# Main_Electronics_B.net
KiCad netlist of a schematic drawn in EAGLE
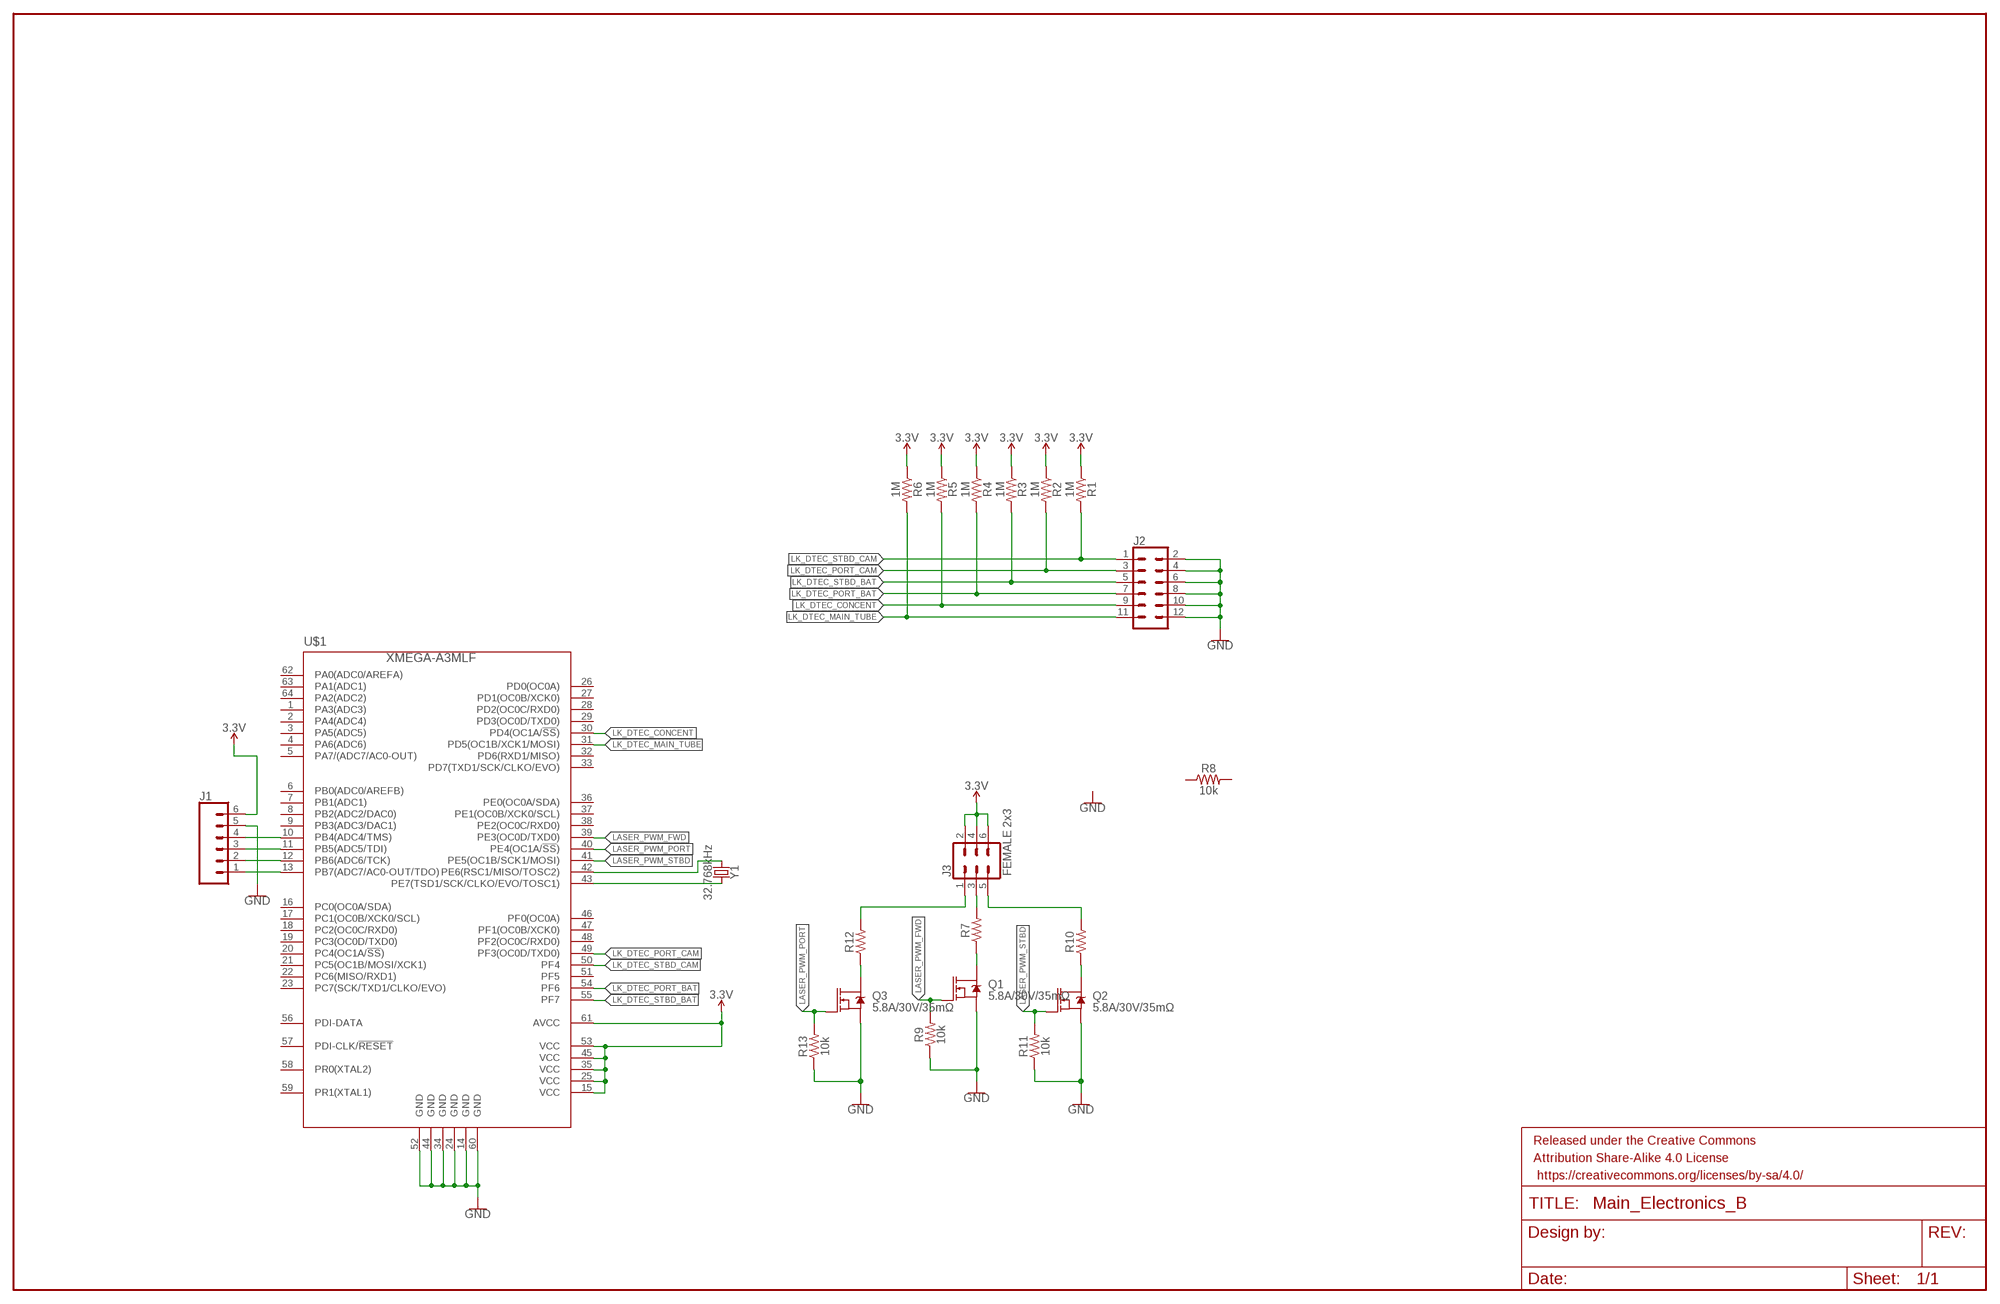
[diagram p0: schematic, sheet 1]

(export (version "E")
  (design (tool "Eeschema 10.0.6"))
  (components
    (comp (ref "FRAME1")
      (value "FRAME-LEDGER")
      (footprint "eagle-import:CREATIVE_COMMONS")
      (libsource (lib "eagle-import") (part "FRAME-LEDGER"))
    )
    (comp (ref "J1")
      (value "CONN_06NO_SILK_NO_POP")
      (footprint "eagle-import:1X06_NO_SILK")
      (libsource (lib "eagle-import") (part "CONN_06NO_SILK_NO_POP"))
    )
    (comp (ref "J2")
      (value "CONN_06X2NO_SILK")
      (footprint "eagle-import:2X6_NOSILK")
      (libsource (lib "eagle-import") (part "CONN_06X2NO_SILK"))
    )
    (comp (ref "J3")
      (value "FEMALE 2x3")
      (footprint "eagle-import:2X3")
      (libsource (lib "eagle-import") (part "CONN_03X2FEMALE"))
    )
    (comp (ref "Q1")
      (value "5.8A/30V/35mΩ")
      (footprint "eagle-import:SOT23-3")
      (libsource (lib "eagle-import") (part "MOSFET-NCH-AO3404A"))
    )
    (comp (ref "Q2")
      (value "5.8A/30V/35mΩ")
      (footprint "eagle-import:SOT23-3")
      (libsource (lib "eagle-import") (part "MOSFET-NCH-AO3404A"))
    )
    (comp (ref "Q3")
      (value "5.8A/30V/35mΩ")
      (footprint "eagle-import:SOT23-3")
      (libsource (lib "eagle-import") (part "MOSFET-NCH-AO3404A"))
    )
    (comp (ref "R1")
      (value "1M")
      (footprint "eagle-import:0603")
      (libsource (lib "eagle-import") (part "1MOHM-0603-1/4W-5%"))
    )
    (comp (ref "R2")
      (value "1M")
      (footprint "eagle-import:0603")
      (libsource (lib "eagle-import") (part "1MOHM-0603-1/4W-5%"))
    )
    (comp (ref "R3")
      (value "1M")
      (footprint "eagle-import:0603")
      (libsource (lib "eagle-import") (part "1MOHM-0603-1/4W-5%"))
    )
    (comp (ref "R4")
      (value "1M")
      (footprint "eagle-import:0603")
      (libsource (lib "eagle-import") (part "1MOHM-0603-1/4W-5%"))
    )
    (comp (ref "R5")
      (value "1M")
      (footprint "eagle-import:0603")
      (libsource (lib "eagle-import") (part "1MOHM-0603-1/4W-5%"))
    )
    (comp (ref "R6")
      (value "1M")
      (footprint "eagle-import:0603")
      (libsource (lib "eagle-import") (part "1MOHM-0603-1/4W-5%"))
    )
    (comp (ref "R7")
      (value "RESISTOR0603")
      (footprint "eagle-import:0603")
      (libsource (lib "eagle-import") (part "RESISTOR0603"))
    )
    (comp (ref "R8")
      (value "10k")
      (footprint "eagle-import:0603")
      (libsource (lib "eagle-import") (part "10KOHM-0603-1/10W-1%"))
    )
    (comp (ref "R9")
      (value "10k")
      (footprint "eagle-import:0603")
      (libsource (lib "eagle-import") (part "10KOHM-0603-1/10W-1%"))
    )
    (comp (ref "R10")
      (value "RESISTOR0603")
      (footprint "eagle-import:0603")
      (libsource (lib "eagle-import") (part "RESISTOR0603"))
    )
    (comp (ref "R11")
      (value "10k")
      (footprint "eagle-import:0603")
      (libsource (lib "eagle-import") (part "10KOHM-0603-1/10W-1%"))
    )
    (comp (ref "R12")
      (value "RESISTOR0603")
      (footprint "eagle-import:0603")
      (libsource (lib "eagle-import") (part "RESISTOR0603"))
    )
    (comp (ref "R13")
      (value "10k")
      (footprint "eagle-import:0603")
      (libsource (lib "eagle-import") (part "10KOHM-0603-1/10W-1%"))
    )
    (comp (ref "U$1")
      (value "XMEGA-A3MLF")
      (footprint "eagle-import:MLF64")
      (libsource (lib "eagle-import") (part "XMEGA-A3MLF"))
    )
    (comp (ref "Y1")
      (value "32.768kHz")
      (footprint "eagle-import:CRYSTAL-PTH-2X6-CYL-KIT")
      (libsource (lib "eagle-import") (part "CRYSTAL-32.768KHZPTH-2X6-KIT"))
    )
  )
  (nets
    (net (code "1") (name "3.3V") (class "Default")
      (node (ref "J1") (pin "6") (pinfunction "6_6") (pintype "passive"))
      (node (ref "J3") (pin "2") (pinfunction "2_2") (pintype "bidirectional"))
      (node (ref "J3") (pin "4") (pinfunction "4_4") (pintype "bidirectional"))
      (node (ref "J3") (pin "6") (pinfunction "6_6") (pintype "bidirectional"))
      (node (ref "R1") (pin "1") (pinfunction "1_1") (pintype "passive"))
      (node (ref "R2") (pin "1") (pinfunction "1_1") (pintype "passive"))
      (node (ref "R3") (pin "1") (pinfunction "1_1") (pintype "passive"))
      (node (ref "R4") (pin "1") (pinfunction "1_1") (pintype "passive"))
      (node (ref "R5") (pin "1") (pinfunction "1_1") (pintype "passive"))
      (node (ref "R6") (pin "1") (pinfunction "1_1") (pintype "passive"))
      (node (ref "U$1") (pin "15") (pinfunction "VCC_15") (pintype "power_in"))
      (node (ref "U$1") (pin "25") (pinfunction "VCC_25") (pintype "power_in"))
      (node (ref "U$1") (pin "35") (pinfunction "VCC_35") (pintype "power_in"))
      (node (ref "U$1") (pin "45") (pinfunction "VCC_45") (pintype "power_in"))
      (node (ref "U$1") (pin "53") (pinfunction "VCC_53") (pintype "power_in"))
      (node (ref "U$1") (pin "61") (pinfunction "AVCC_61") (pintype "power_in"))
    )
    (net (code "2") (name "GND") (class "Default")
      (node (ref "J1") (pin "5") (pinfunction "5_5") (pintype "passive"))
      (node (ref "J2") (pin "10") (pinfunction "10_10") (pintype "passive"))
      (node (ref "J2") (pin "12") (pinfunction "12_12") (pintype "passive"))
      (node (ref "J2") (pin "2") (pinfunction "2_2") (pintype "passive"))
      (node (ref "J2") (pin "4") (pinfunction "4_4") (pintype "passive"))
      (node (ref "J2") (pin "6") (pinfunction "6_6") (pintype "passive"))
      (node (ref "J2") (pin "8") (pinfunction "8_8") (pintype "passive"))
      (node (ref "Q1") (pin "2") (pinfunction "S_2") (pintype "bidirectional"))
      (node (ref "Q2") (pin "2") (pinfunction "S_2") (pintype "bidirectional"))
      (node (ref "Q3") (pin "2") (pinfunction "S_2") (pintype "bidirectional"))
      (node (ref "R11") (pin "1") (pinfunction "1_1") (pintype "passive"))
      (node (ref "R13") (pin "1") (pinfunction "1_1") (pintype "passive"))
      (node (ref "R9") (pin "1") (pinfunction "1_1") (pintype "passive"))
      (node (ref "U$1") (pin "14") (pinfunction "GND_14") (pintype "power_in"))
      (node (ref "U$1") (pin "24") (pinfunction "GND_24") (pintype "power_in"))
      (node (ref "U$1") (pin "34") (pinfunction "GND_34") (pintype "power_in"))
      (node (ref "U$1") (pin "44") (pinfunction "GND_44") (pintype "power_in"))
      (node (ref "U$1") (pin "52") (pinfunction "GND_52") (pintype "power_in"))
      (node (ref "U$1") (pin "60") (pinfunction "GND_60") (pintype "power_in"))
    )
    (net (code "3") (name "LASER_PWM_FWD") (class "Default")
      (node (ref "Q1") (pin "1") (pinfunction "G_1") (pintype "bidirectional"))
      (node (ref "R9") (pin "2") (pinfunction "2_2") (pintype "passive"))
      (node (ref "U$1") (pin "39") (pinfunction "PE3(OC0D/TXD0)_39") (pintype "bidirectional"))
    )
    (net (code "4") (name "LASER_PWM_PORT") (class "Default")
      (node (ref "Q3") (pin "1") (pinfunction "G_1") (pintype "bidirectional"))
      (node (ref "R13") (pin "2") (pinfunction "2_2") (pintype "passive"))
      (node (ref "U$1") (pin "40") (pinfunction "PE4(OC1A/~{SS})_40") (pintype "bidirectional"))
    )
    (net (code "5") (name "LASER_PWM_STBD") (class "Default")
      (node (ref "Q2") (pin "1") (pinfunction "G_1") (pintype "bidirectional"))
      (node (ref "R11") (pin "2") (pinfunction "2_2") (pintype "passive"))
      (node (ref "U$1") (pin "41") (pinfunction "PE5(OC1B/SCK1/MOSI)_41") (pintype "bidirectional"))
    )
    (net (code "6") (name "LK_DTEC_CONCENT") (class "Default")
      (node (ref "J2") (pin "9") (pinfunction "9_9") (pintype "passive"))
      (node (ref "R5") (pin "2") (pinfunction "2_2") (pintype "passive"))
      (node (ref "U$1") (pin "30") (pinfunction "PD4(OC1A/~{SS})_30") (pintype "bidirectional"))
    )
    (net (code "7") (name "LK_DTEC_MAIN_TUBE") (class "Default")
      (node (ref "J2") (pin "11") (pinfunction "11_11") (pintype "passive"))
      (node (ref "R6") (pin "2") (pinfunction "2_2") (pintype "passive"))
      (node (ref "U$1") (pin "31") (pinfunction "PD5(OC1B/XCK1/MOSI)_31") (pintype "bidirectional"))
    )
    (net (code "8") (name "LK_DTEC_PORT_BAT") (class "Default")
      (node (ref "J2") (pin "7") (pinfunction "7_7") (pintype "passive"))
      (node (ref "R4") (pin "2") (pinfunction "2_2") (pintype "passive"))
      (node (ref "U$1") (pin "54") (pinfunction "PF6_54") (pintype "bidirectional"))
    )
    (net (code "9") (name "LK_DTEC_PORT_CAM") (class "Default")
      (node (ref "J2") (pin "3") (pinfunction "3_3") (pintype "passive"))
      (node (ref "R2") (pin "2") (pinfunction "2_2") (pintype "passive"))
      (node (ref "U$1") (pin "49") (pinfunction "PF3(OC0D/TXD0)_49") (pintype "bidirectional"))
    )
    (net (code "10") (name "LK_DTEC_STBD_BAT") (class "Default")
      (node (ref "J2") (pin "5") (pinfunction "5_5") (pintype "passive"))
      (node (ref "R3") (pin "2") (pinfunction "2_2") (pintype "passive"))
      (node (ref "U$1") (pin "55") (pinfunction "PF7_55") (pintype "bidirectional"))
    )
    (net (code "11") (name "LK_DTEC_STBD_CAM") (class "Default")
      (node (ref "J2") (pin "1") (pinfunction "1_1") (pintype "passive"))
      (node (ref "R1") (pin "2") (pinfunction "2_2") (pintype "passive"))
      (node (ref "U$1") (pin "50") (pinfunction "PF4_50") (pintype "bidirectional"))
    )
    (net (code "12") (name "Net-(J3-Pad1)") (class "Default")
      (node (ref "J3") (pin "1") (pinfunction "1_1") (pintype "bidirectional"))
      (node (ref "R12") (pin "2") (pinfunction "2_2") (pintype "passive"))
    )
    (net (code "13") (name "Net-(J3-Pad3)") (class "Default")
      (node (ref "J3") (pin "3") (pinfunction "3_3") (pintype "bidirectional"))
      (node (ref "R7") (pin "2") (pinfunction "2_2") (pintype "passive"))
    )
    (net (code "14") (name "Net-(J3-Pad5)") (class "Default")
      (node (ref "J3") (pin "5") (pinfunction "5_5") (pintype "bidirectional"))
      (node (ref "R10") (pin "2") (pinfunction "2_2") (pintype "passive"))
    )
    (net (code "15") (name "Net-(Q1-D)") (class "Default")
      (node (ref "Q1") (pin "3") (pinfunction "D_3") (pintype "bidirectional"))
      (node (ref "R7") (pin "1") (pinfunction "1_1") (pintype "passive"))
    )
    (net (code "16") (name "Net-(Q2-D)") (class "Default")
      (node (ref "Q2") (pin "3") (pinfunction "D_3") (pintype "bidirectional"))
      (node (ref "R10") (pin "1") (pinfunction "1_1") (pintype "passive"))
    )
    (net (code "17") (name "Net-(Q3-D)") (class "Default")
      (node (ref "Q3") (pin "3") (pinfunction "D_3") (pintype "bidirectional"))
      (node (ref "R12") (pin "1") (pinfunction "1_1") (pintype "passive"))
    )
    (net (code "18") (name "Net-(U$1-PB4(ADC4{slash}TMS))") (class "Default")
      (node (ref "J1") (pin "4") (pinfunction "4_4") (pintype "passive"))
      (node (ref "U$1") (pin "10") (pinfunction "PB4(ADC4/TMS)_10") (pintype "bidirectional"))
    )
    (net (code "19") (name "Net-(U$1-PB5(ADC5{slash}TDI))") (class "Default")
      (node (ref "J1") (pin "3") (pinfunction "3_3") (pintype "passive"))
      (node (ref "U$1") (pin "11") (pinfunction "PB5(ADC5/TDI)_11") (pintype "bidirectional"))
    )
    (net (code "20") (name "Net-(U$1-PB6(ADC6{slash}TCK))") (class "Default")
      (node (ref "J1") (pin "2") (pinfunction "2_2") (pintype "passive"))
      (node (ref "U$1") (pin "12") (pinfunction "PB6(ADC6/TCK)_12") (pintype "bidirectional"))
    )
    (net (code "21") (name "Net-(U$1-PB7(ADC7{slash}AC0-OUT{slash}TDO))") (class "Default")
      (node (ref "J1") (pin "1") (pinfunction "1_1") (pintype "passive"))
      (node (ref "U$1") (pin "13") (pinfunction "PB7(ADC7/AC0-OUT/TDO)_13") (pintype "bidirectional"))
    )
    (net (code "22") (name "Net-(U$1-PE6(RSC1{slash}MISO{slash}TOSC2))") (class "Default")
      (node (ref "U$1") (pin "42") (pinfunction "PE6(RSC1/MISO/TOSC2)_42") (pintype "bidirectional"))
      (node (ref "Y1") (pin "1") (pinfunction "1_1") (pintype "passive"))
    )
    (net (code "23") (name "Net-(U$1-PE7(TSD1{slash}SCK{slash}CLKO{slash}EVO{slash}TOSC1))") (class "Default")
      (node (ref "U$1") (pin "43") (pinfunction "PE7(TSD1/SCK/CLKO/EVO/TOSC1)_43") (pintype "bidirectional"))
      (node (ref "Y1") (pin "2") (pinfunction "2_2") (pintype "passive"))
    )
    (net (code "24") (name "unconnected-(R8-Pad1)") (class "Default")
      (node (ref "R8") (pin "1") (pinfunction "1_1") (pintype "passive"))
    )
    (net (code "25") (name "unconnected-(R8-Pad2)") (class "Default")
      (node (ref "R8") (pin "2") (pinfunction "2_2") (pintype "passive"))
    )
    (net (code "26") (name "unconnected-(U$1-PA0(ADC0{slash}AREFA)-Pad62)") (class "Default")
      (node (ref "U$1") (pin "62") (pinfunction "PA0(ADC0/AREFA)_62") (pintype "bidirectional"))
    )
    (net (code "27") (name "unconnected-(U$1-PA1(ADC1)-Pad63)") (class "Default")
      (node (ref "U$1") (pin "63") (pinfunction "PA1(ADC1)_63") (pintype "bidirectional"))
    )
    (net (code "28") (name "unconnected-(U$1-PA2(ADC2)-Pad64)") (class "Default")
      (node (ref "U$1") (pin "64") (pinfunction "PA2(ADC2)_64") (pintype "bidirectional"))
    )
    (net (code "29") (name "unconnected-(U$1-PA3(ADC3)-Pad1)") (class "Default")
      (node (ref "U$1") (pin "1") (pinfunction "PA3(ADC3)_1") (pintype "bidirectional"))
    )
    (net (code "30") (name "unconnected-(U$1-PA4(ADC4)-Pad2)") (class "Default")
      (node (ref "U$1") (pin "2") (pinfunction "PA4(ADC4)_2") (pintype "bidirectional"))
    )
    (net (code "31") (name "unconnected-(U$1-PA5(ADC5)-Pad3)") (class "Default")
      (node (ref "U$1") (pin "3") (pinfunction "PA5(ADC5)_3") (pintype "bidirectional"))
    )
    (net (code "32") (name "unconnected-(U$1-PA6(ADC6)-Pad4)") (class "Default")
      (node (ref "U$1") (pin "4") (pinfunction "PA6(ADC6)_4") (pintype "bidirectional"))
    )
    (net (code "33") (name "unconnected-(U$1-PA7{slash}(ADC7{slash}AC0-OUT)-Pad5)") (class "Default")
      (node (ref "U$1") (pin "5") (pinfunction "PA7/(ADC7/AC0-OUT)_5") (pintype "bidirectional"))
    )
    (net (code "34") (name "unconnected-(U$1-PB0(ADC0{slash}AREFB)-Pad6)") (class "Default")
      (node (ref "U$1") (pin "6") (pinfunction "PB0(ADC0/AREFB)_6") (pintype "bidirectional"))
    )
    (net (code "35") (name "unconnected-(U$1-PB1(ADC1)-Pad7)") (class "Default")
      (node (ref "U$1") (pin "7") (pinfunction "PB1(ADC1)_7") (pintype "bidirectional"))
    )
    (net (code "36") (name "unconnected-(U$1-PB2(ADC2{slash}DAC0)-Pad8)") (class "Default")
      (node (ref "U$1") (pin "8") (pinfunction "PB2(ADC2/DAC0)_8") (pintype "bidirectional"))
    )
    (net (code "37") (name "unconnected-(U$1-PB3(ADC3{slash}DAC1)-Pad9)") (class "Default")
      (node (ref "U$1") (pin "9") (pinfunction "PB3(ADC3/DAC1)_9") (pintype "bidirectional"))
    )
    (net (code "38") (name "unconnected-(U$1-PC0(OC0A{slash}SDA)-Pad16)") (class "Default")
      (node (ref "U$1") (pin "16") (pinfunction "PC0(OC0A/SDA)_16") (pintype "bidirectional"))
    )
    (net (code "39") (name "unconnected-(U$1-PC1(OC0B{slash}XCK0{slash}SCL)-Pad17)") (class "Default")
      (node (ref "U$1") (pin "17") (pinfunction "PC1(OC0B/XCK0/SCL)_17") (pintype "bidirectional"))
    )
    (net (code "40") (name "unconnected-(U$1-PC2(OC0C{slash}RXD0)-Pad18)") (class "Default")
      (node (ref "U$1") (pin "18") (pinfunction "PC2(OC0C/RXD0)_18") (pintype "bidirectional"))
    )
    (net (code "41") (name "unconnected-(U$1-PC3(OC0D{slash}TXD0)-Pad19)") (class "Default")
      (node (ref "U$1") (pin "19") (pinfunction "PC3(OC0D/TXD0)_19") (pintype "bidirectional"))
    )
    (net (code "42") (name "unconnected-(U$1-PC4(OC1A{slash}~{SS})-Pad20)") (class "Default")
      (node (ref "U$1") (pin "20") (pinfunction "PC4(OC1A/~{SS})_20") (pintype "bidirectional"))
    )
    (net (code "43") (name "unconnected-(U$1-PC5(OC1B{slash}MOSI{slash}XCK1)-Pad21)") (class "Default")
      (node (ref "U$1") (pin "21") (pinfunction "PC5(OC1B/MOSI/XCK1)_21") (pintype "bidirectional"))
    )
    (net (code "44") (name "unconnected-(U$1-PC6(MISO{slash}RXD1)-Pad22)") (class "Default")
      (node (ref "U$1") (pin "22") (pinfunction "PC6(MISO/RXD1)_22") (pintype "bidirectional"))
    )
    (net (code "45") (name "unconnected-(U$1-PC7(SCK{slash}TXD1{slash}CLKO{slash}EVO)-Pad23)") (class "Default")
      (node (ref "U$1") (pin "23") (pinfunction "PC7(SCK/TXD1/CLKO/EVO)_23") (pintype "bidirectional"))
    )
    (net (code "46") (name "unconnected-(U$1-PD0(OC0A)-Pad26)") (class "Default")
      (node (ref "U$1") (pin "26") (pinfunction "PD0(OC0A)_26") (pintype "bidirectional"))
    )
    (net (code "47") (name "unconnected-(U$1-PD1(OC0B{slash}XCK0)-Pad27)") (class "Default")
      (node (ref "U$1") (pin "27") (pinfunction "PD1(OC0B/XCK0)_27") (pintype "bidirectional"))
    )
    (net (code "48") (name "unconnected-(U$1-PD2(OC0C{slash}RXD0)-Pad28)") (class "Default")
      (node (ref "U$1") (pin "28") (pinfunction "PD2(OC0C/RXD0)_28") (pintype "bidirectional"))
    )
    (net (code "49") (name "unconnected-(U$1-PD3(OC0D{slash}TXD0)-Pad29)") (class "Default")
      (node (ref "U$1") (pin "29") (pinfunction "PD3(OC0D/TXD0)_29") (pintype "bidirectional"))
    )
    (net (code "50") (name "unconnected-(U$1-PD6(RXD1{slash}MISO)-Pad32)") (class "Default")
      (node (ref "U$1") (pin "32") (pinfunction "PD6(RXD1/MISO)_32") (pintype "bidirectional"))
    )
    (net (code "51") (name "unconnected-(U$1-PD7(TXD1{slash}SCK{slash}CLKO{slash}EVO)-Pad33)") (class "Default")
      (node (ref "U$1") (pin "33") (pinfunction "PD7(TXD1/SCK/CLKO/EVO)_33") (pintype "bidirectional"))
    )
    (net (code "52") (name "unconnected-(U$1-PDI-CLK{slash}~{RESET}-Pad57)") (class "Default")
      (node (ref "U$1") (pin "57") (pinfunction "PDI-CLK/~{RESET}_57") (pintype "input"))
    )
    (net (code "53") (name "unconnected-(U$1-PDI-DATA-Pad56)") (class "Default")
      (node (ref "U$1") (pin "56") (pinfunction "PDI-DATA_56") (pintype "bidirectional"))
    )
    (net (code "54") (name "unconnected-(U$1-PE0(OC0A{slash}SDA)-Pad36)") (class "Default")
      (node (ref "U$1") (pin "36") (pinfunction "PE0(OC0A/SDA)_36") (pintype "bidirectional"))
    )
    (net (code "55") (name "unconnected-(U$1-PE1(OC0B{slash}XCK0{slash}SCL)-Pad37)") (class "Default")
      (node (ref "U$1") (pin "37") (pinfunction "PE1(OC0B/XCK0/SCL)_37") (pintype "bidirectional"))
    )
    (net (code "56") (name "unconnected-(U$1-PE2(OC0C{slash}RXD0)-Pad38)") (class "Default")
      (node (ref "U$1") (pin "38") (pinfunction "PE2(OC0C/RXD0)_38") (pintype "bidirectional"))
    )
    (net (code "57") (name "unconnected-(U$1-PF0(OC0A)-Pad46)") (class "Default")
      (node (ref "U$1") (pin "46") (pinfunction "PF0(OC0A)_46") (pintype "bidirectional"))
    )
    (net (code "58") (name "unconnected-(U$1-PF1(OC0B{slash}XCK0)-Pad47)") (class "Default")
      (node (ref "U$1") (pin "47") (pinfunction "PF1(OC0B/XCK0)_47") (pintype "bidirectional"))
    )
    (net (code "59") (name "unconnected-(U$1-PF2(OC0C{slash}RXD0)-Pad48)") (class "Default")
      (node (ref "U$1") (pin "48") (pinfunction "PF2(OC0C/RXD0)_48") (pintype "bidirectional"))
    )
    (net (code "60") (name "unconnected-(U$1-PF5-Pad51)") (class "Default")
      (node (ref "U$1") (pin "51") (pinfunction "PF5_51") (pintype "bidirectional"))
    )
    (net (code "61") (name "unconnected-(U$1-PR0(XTAL2)-Pad58)") (class "Default")
      (node (ref "U$1") (pin "58") (pinfunction "PR0(XTAL2)_58") (pintype "bidirectional"))
    )
    (net (code "62") (name "unconnected-(U$1-PR1(XTAL1)-Pad59)") (class "Default")
      (node (ref "U$1") (pin "59") (pinfunction "PR1(XTAL1)_59") (pintype "bidirectional"))
    )
  )
)
